# Main.net
KiCad netlist of a schematic drawn in Altium Designer
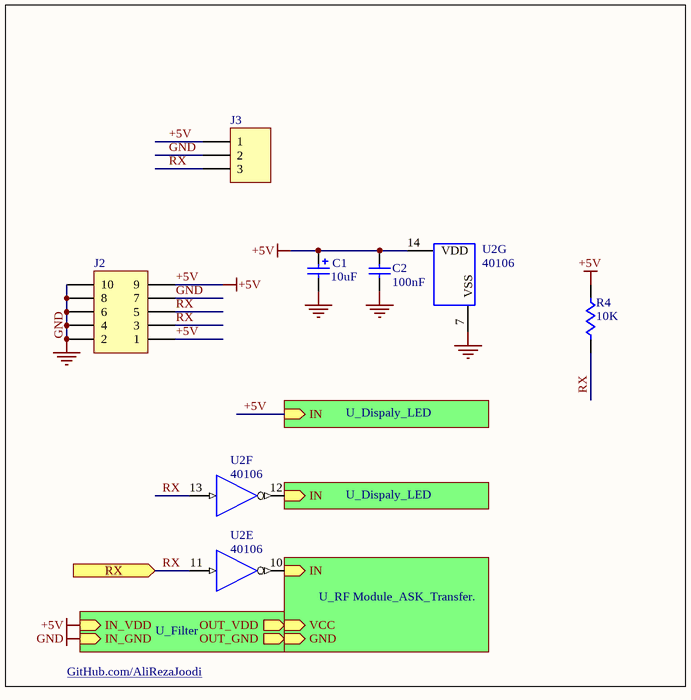
[diagram p0: Main.SchDoc]

(export (version "E")
  (design (tool "Eeschema 10.0.6"))
  (components
    (comp (ref "C1")
      (value "10uF")
      (footprint "CAPPR2.5-6.3x5")
      (description "Polarized Capacitor (Radial)")
      (fields (field (name "MANUFACTURER") "Generic Components") (field (name "PUBLISHER") "Altium Limited"))
      (libsource (lib "Miscellaneous Devices") (part "Cap Pol1"))
    )
    (comp (ref "C2")
      (value "100nF")
      (footprint "CAPNTO2.54-3.05x1.78A")
      (description "Capacitor")
      (fields (field (name "MANUFACTURER") "Generic Components") (field (name "PUBLISHER") "Altium Limited"))
      (libsource (lib "Miscellaneous Devices") (part "Cap"))
    )
    (comp (ref "J2")
      (value "Header 5X2")
      (footprint "FKV10SN")
      (description "Header, 5-Pin, Dual row")
      (fields (field (name "MANUFACTURER") "Generic Components") (field (name "PUBLISHER") "Altium Limited"))
      (libsource (lib "Miscellaneous Connectors") (part "Header 5X2"))
    )
    (comp (ref "J3")
      (value "3PIN")
      (footprint "PIN3")
      (description "Header, 3-Pin,  Right Angle")
      (fields (field (name "MANUFACTURER") "Generic Components") (field (name "PUBLISHER") "Altium Limited"))
      (libsource (lib "Miscellaneous Connectors") (part "Header 3H"))
    )
    (comp (ref "R4")
      (value "10K")
      (footprint "AXIAL-0.4")
      (description "Resistor")
      (fields (field (name "MANUFACTURER") "Generic Components") (field (name "PUBLISHER") "Altium Limited"))
      (libsource (lib "Miscellaneous Devices") (part "Res1"))
    )
    (comp (ref "U2")
      (value "40106")
      (footprint "DIP14")
      (description "Hex inverting Schmitt trigger, 14-Pin")
      (fields (field (name "PUBLISHER") "Altium Limited"))
      (libsource (lib "my Libraries") (part "40106"))
    )
  )
  (nets
    (net (code "1") (name "+5V") (class "Default")
      (node (ref "C1") (pin "1") (pinfunction "1_1") (pintype "passive"))
      (node (ref "C2") (pin "2") (pinfunction "2_2") (pintype "passive"))
      (node (ref "J2") (pin "1") (pinfunction "1_1") (pintype "passive"))
      (node (ref "J2") (pin "9") (pinfunction "9_9") (pintype "passive"))
      (node (ref "J3") (pin "1") (pinfunction "1_1") (pintype "passive"))
      (node (ref "R4") (pin "1") (pinfunction "1_1") (pintype "passive"))
      (node (ref "U2") (pin "14") (pinfunction "VDD_14") (pintype "passive"))
    )
    (net (code "2") (name "/IN") (class "Default")
      (node (ref "U2") (pin "10") (pinfunction "~{O}_10") (pintype "output"))
    )
    (net (code "3") (name "/IN_1") (class "Default")
      (node (ref "U2") (pin "12") (pinfunction "~{O}_12") (pintype "output"))
    )
    (net (code "6") (name "/RX") (class "Default")
      (node (ref "J2") (pin "3") (pinfunction "3_3") (pintype "passive"))
      (node (ref "J2") (pin "5") (pinfunction "5_5") (pintype "passive"))
      (node (ref "J3") (pin "3") (pinfunction "3_3") (pintype "passive"))
      (node (ref "R4") (pin "2") (pinfunction "2_2") (pintype "passive"))
      (node (ref "U2") (pin "11") (pinfunction "I_11") (pintype "input"))
      (node (ref "U2") (pin "13") (pinfunction "I_13") (pintype "input"))
    )
    (net (code "7") (name "GND") (class "Default")
      (node (ref "C1") (pin "2") (pinfunction "2_2") (pintype "passive"))
      (node (ref "C2") (pin "1") (pinfunction "1_1") (pintype "passive"))
      (node (ref "J2") (pin "10") (pinfunction "10_10") (pintype "passive"))
      (node (ref "J2") (pin "2") (pinfunction "2_2") (pintype "passive"))
      (node (ref "J2") (pin "4") (pinfunction "4_4") (pintype "passive"))
      (node (ref "J2") (pin "6") (pinfunction "6_6") (pintype "passive"))
      (node (ref "J2") (pin "7") (pinfunction "7_7") (pintype "passive"))
      (node (ref "J2") (pin "8") (pinfunction "8_8") (pintype "passive"))
      (node (ref "J3") (pin "2") (pinfunction "2_2") (pintype "passive"))
      (node (ref "U2") (pin "7") (pinfunction "VSS_7") (pintype "power_in"))
    )
  )
)
